# untitled.net
KiCad netlist of a schematic drawn in EAGLE
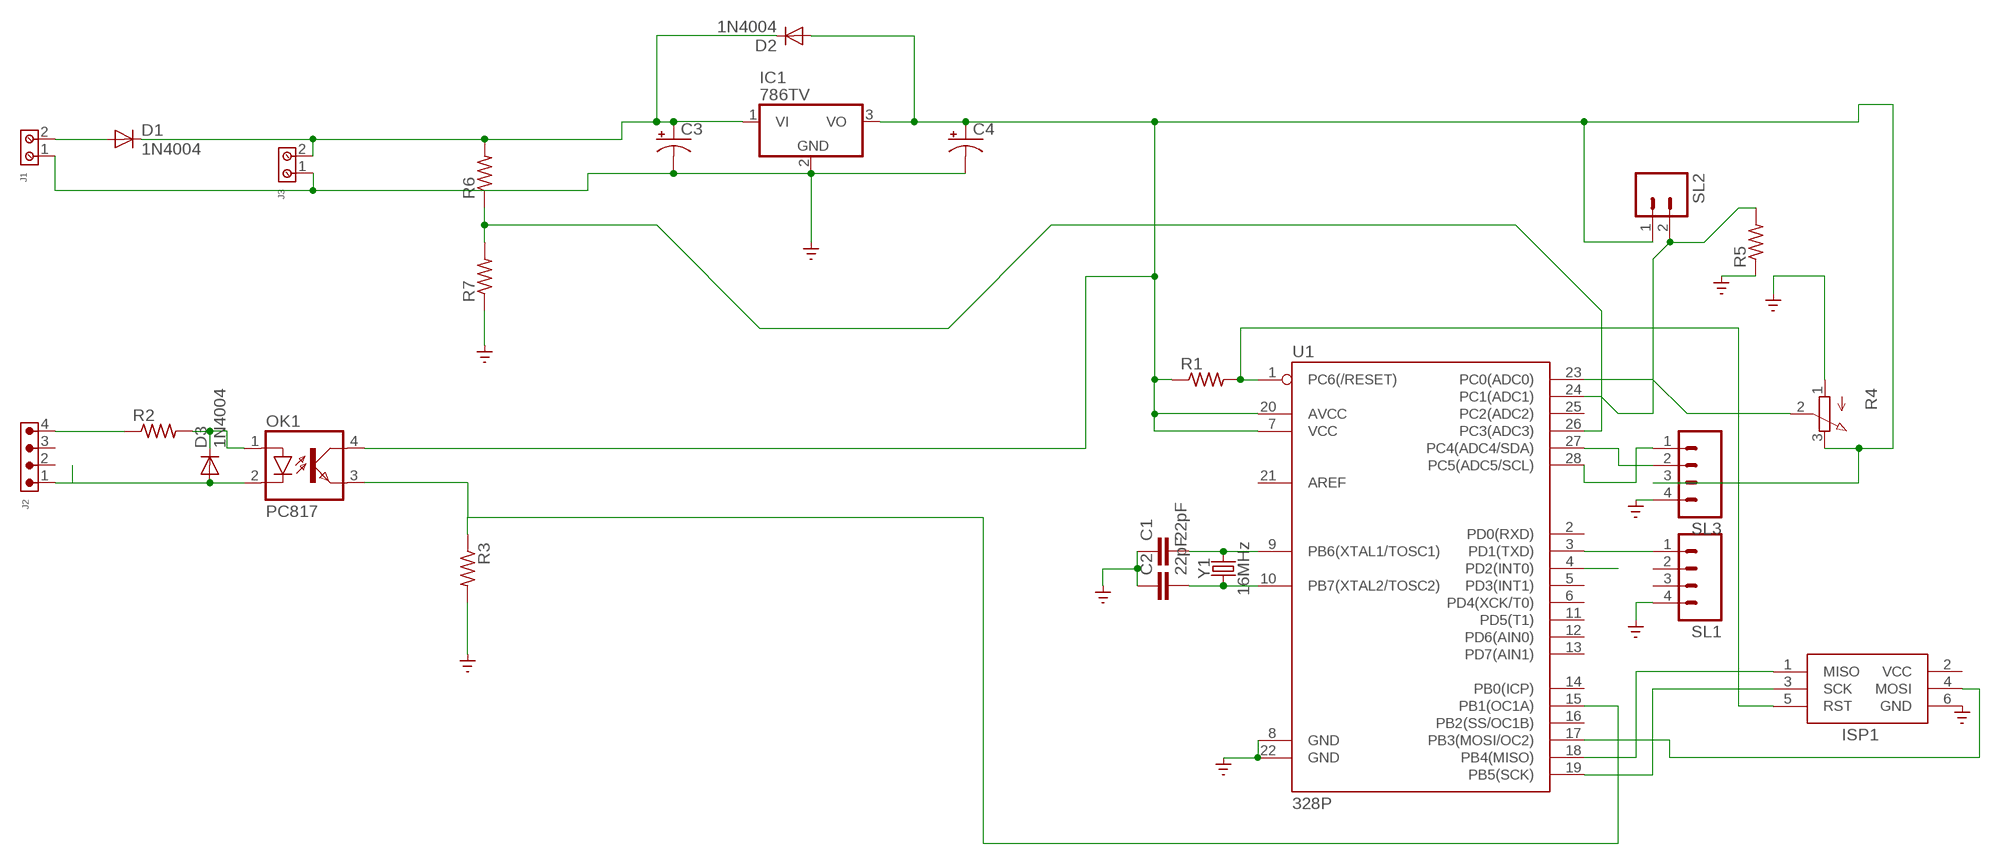
[diagram p0: schematic, sheet 1]

(export (version "E")
  (design (tool "Eeschema 10.0.6"))
  (components
    (comp (ref "C1")
      (value "22pF")
      (footprint "eagle-import:CAP-PTH-2.54")
      (libsource (lib "eagle-import") (part "22PF-PTH-2.54MM-200V-5%"))
    )
    (comp (ref "C2")
      (value "22pF")
      (footprint "eagle-import:CAP-PTH-2.54")
      (libsource (lib "eagle-import") (part "22PF-PTH-2.54MM-200V-5%"))
    )
    (comp (ref "C3")
      (value "CAPACITOR-PE5-10.5")
      (footprint "eagle-import:E5-10,5")
      (libsource (lib "eagle-import") (part "CAPACITOR-PE5-10.5"))
    )
    (comp (ref "C4")
      (value "CAPACITOR-PE5-6")
      (footprint "eagle-import:E5-6")
      (libsource (lib "eagle-import") (part "CAPACITOR-PE5-6"))
    )
    (comp (ref "D1")
      (value "1N4004")
      (footprint "eagle-import:DO41-10")
      (libsource (lib "eagle-import") (part "1N4004"))
    )
    (comp (ref "D2")
      (value "1N4004")
      (footprint "eagle-import:DO41-10")
      (libsource (lib "eagle-import") (part "1N4004"))
    )
    (comp (ref "D3")
      (value "1N4004")
      (footprint "eagle-import:DO41-10")
      (libsource (lib "eagle-import") (part "1N4004"))
    )
    (comp (ref "IC1")
      (value "786TV")
      (footprint "eagle-import:TO220V")
      (libsource (lib "eagle-import") (part "78TV6"))
    )
    (comp (ref "ISP1")
      (value "AVRISP-6")
      (footprint "eagle-import:AVRISP")
      (libsource (lib "eagle-import") (part "AVRISP-6"))
    )
    (comp (ref "J1")
      (value "691213710002")
      (footprint "eagle-import:691213710002")
      (libsource (lib "eagle-import") (part "691213710002"))
    )
    (comp (ref "J2")
      (value "691305530004")
      (footprint "eagle-import:691305530004")
      (libsource (lib "eagle-import") (part "691305530004"))
    )
    (comp (ref "J3")
      (value "691213710002")
      (footprint "eagle-import:691213710002")
      (libsource (lib "eagle-import") (part "691213710002"))
    )
    (comp (ref "OK1")
      (value "PC817")
      (footprint "eagle-import:DIL04")
      (fields (field (name "MPN") "PC817X4J000F"))
      (libsource (lib "eagle-import") (part "PC817"))
    )
    (comp (ref "R1")
      (value "R-US_0207/9")
      (footprint "eagle-import:0207_9")
      (libsource (lib "eagle-import") (part "R-US_0207/9"))
    )
    (comp (ref "R2")
      (value "R-US_0207/9")
      (footprint "eagle-import:0207_9")
      (libsource (lib "eagle-import") (part "R-US_0207/9"))
    )
    (comp (ref "R3")
      (value "R-US_0207/9")
      (footprint "eagle-import:0207_9")
      (libsource (lib "eagle-import") (part "R-US_0207/9"))
    )
    (comp (ref "R4")
      (value "3RP/1610N")
      (footprint "eagle-import:3RP_1610N")
      (libsource (lib "eagle-import") (part "3RP/1610N"))
    )
    (comp (ref "R5")
      (value "R-US_0207/9")
      (footprint "eagle-import:0207_9")
      (libsource (lib "eagle-import") (part "R-US_0207/9"))
    )
    (comp (ref "R6")
      (value "R-US_0207/9")
      (footprint "eagle-import:0207_9")
      (libsource (lib "eagle-import") (part "R-US_0207/9"))
    )
    (comp (ref "R7")
      (value "R-US_0207/9")
      (footprint "eagle-import:0207_9")
      (libsource (lib "eagle-import") (part "R-US_0207/9"))
    )
    (comp (ref "SL1")
      (value "M04")
      (footprint "eagle-import:04P")
      (libsource (lib "eagle-import") (part "M04"))
    )
    (comp (ref "SL2")
      (value "M02")
      (footprint "eagle-import:02P")
      (libsource (lib "eagle-import") (part "M02"))
    )
    (comp (ref "SL3")
      (value "M04")
      (footprint "eagle-import:04P")
      (libsource (lib "eagle-import") (part "M04"))
    )
    (comp (ref "U1")
      (value "328P")
      (footprint "eagle-import:DIP28")
      (libsource (lib "eagle-import") (part "ATMEGA328P_PDIP"))
    )
    (comp (ref "Y1")
      (value "16MHz")
      (footprint "eagle-import:HC49US")
      (libsource (lib "eagle-import") (part "CRYSTAL-16MHZPTH-HC49US"))
    )
  )
  (nets
    (net (code "1") (name "/VCC") (class "Default")
      (node (ref "ISP1") (pin "2") (pinfunction "VCC_2") (pintype "power_in"))
    )
    (net (code "2") (name "Net-(D1-PadA)") (class "Default")
      (node (ref "D1") (pin "A") (pinfunction "A_A") (pintype "passive"))
      (node (ref "J1") (pin "2") (pinfunction "2_2") (pintype "passive"))
    )
    (net (code "3") (name "Net-(IC1-VI)") (class "Default")
      (node (ref "C3") (pin "+") (pinfunction "+_+") (pintype "passive"))
      (node (ref "D1") (pin "C") (pinfunction "C_C") (pintype "passive"))
      (node (ref "D2") (pin "C") (pinfunction "C_C") (pintype "passive"))
      (node (ref "IC1") (pin "1") (pinfunction "VI_1") (pintype "input"))
      (node (ref "J3") (pin "2") (pinfunction "2_2") (pintype "passive"))
      (node (ref "R6") (pin "2") (pinfunction "2_2") (pintype "passive"))
    )
    (net (code "4") (name "Net-(IC1-VO)") (class "Default")
      (node (ref "C4") (pin "+") (pinfunction "+_+") (pintype "passive"))
      (node (ref "D2") (pin "A") (pinfunction "A_A") (pintype "passive"))
      (node (ref "IC1") (pin "3") (pinfunction "VO_3") (pintype "passive"))
      (node (ref "OK1") (pin "4") (pinfunction "COL_4") (pintype "passive"))
      (node (ref "R1") (pin "1") (pinfunction "1_1") (pintype "passive"))
      (node (ref "R4") (pin "3") (pinfunction "E_3") (pintype "passive"))
      (node (ref "SL2") (pin "1") (pinfunction "1_1") (pintype "passive"))
      (node (ref "SL3") (pin "3") (pinfunction "3_3") (pintype "passive"))
      (node (ref "U1") (pin "20") (pinfunction "AVCC_20") (pintype "bidirectional"))
      (node (ref "U1") (pin "7") (pinfunction "VCC_7") (pintype "bidirectional"))
    )
    (net (code "5") (name "Net-(ISP1-MISO)") (class "Default")
      (node (ref "ISP1") (pin "1") (pinfunction "MISO_1") (pintype "input"))
      (node (ref "U1") (pin "18") (pinfunction "PB4(MISO)_18") (pintype "bidirectional"))
    )
    (net (code "6") (name "Net-(ISP1-MOSI)") (class "Default")
      (node (ref "ISP1") (pin "4") (pinfunction "MOSI_4") (pintype "output"))
      (node (ref "U1") (pin "17") (pinfunction "PB3(MOSI/OC2)_17") (pintype "bidirectional"))
    )
    (net (code "7") (name "Net-(ISP1-RST)") (class "Default")
      (node (ref "ISP1") (pin "5") (pinfunction "RST_5") (pintype "output"))
      (node (ref "R1") (pin "2") (pinfunction "2_2") (pintype "passive"))
      (node (ref "U1") (pin "1") (pinfunction "PC6(/RESET)_1") (pintype "bidirectional"))
    )
    (net (code "8") (name "Net-(ISP1-SCK)") (class "Default")
      (node (ref "ISP1") (pin "3") (pinfunction "SCK_3") (pintype "output"))
      (node (ref "U1") (pin "19") (pinfunction "PB5(SCK)_19") (pintype "bidirectional"))
    )
    (net (code "9") (name "Net-(J2-Pad4)") (class "Default")
      (node (ref "J2") (pin "4") (pinfunction "4_4") (pintype "passive"))
      (node (ref "R2") (pin "1") (pinfunction "1_1") (pintype "passive"))
    )
    (net (code "10") (name "Net-(OK1-A)") (class "Default")
      (node (ref "D3") (pin "C") (pinfunction "C_C") (pintype "passive"))
      (node (ref "OK1") (pin "1") (pinfunction "A_1") (pintype "passive"))
      (node (ref "R2") (pin "2") (pinfunction "2_2") (pintype "passive"))
    )
    (net (code "11") (name "Net-(OK1-C)") (class "Default")
      (node (ref "D3") (pin "A") (pinfunction "A_A") (pintype "passive"))
      (node (ref "J2") (pin "1") (pinfunction "1_1") (pintype "passive"))
      (node (ref "OK1") (pin "2") (pinfunction "C_2") (pintype "passive"))
    )
    (net (code "12") (name "Net-(OK1-EMIT)") (class "Default")
      (node (ref "OK1") (pin "3") (pinfunction "EMIT_3") (pintype "passive"))
      (node (ref "R3") (pin "1") (pinfunction "1_1") (pintype "passive"))
      (node (ref "U1") (pin "15") (pinfunction "PB1(OC1A)_15") (pintype "bidirectional"))
    )
    (net (code "13") (name "Net-(R4-S)") (class "Default")
      (node (ref "R4") (pin "2") (pinfunction "S_2") (pintype "passive"))
      (node (ref "U1") (pin "23") (pinfunction "PC0(ADC0)_23") (pintype "bidirectional"))
    )
    (net (code "14") (name "Net-(U1-PB6(XTAL1{slash}TOSC1))") (class "Default")
      (node (ref "C1") (pin "2") (pinfunction "2_2") (pintype "passive"))
      (node (ref "U1") (pin "9") (pinfunction "PB6(XTAL1/TOSC1)_9") (pintype "bidirectional"))
      (node (ref "Y1") (pin "2") (pinfunction "2_2") (pintype "passive"))
    )
    (net (code "15") (name "Net-(U1-PB7(XTAL2{slash}TOSC2))") (class "Default")
      (node (ref "C2") (pin "2") (pinfunction "2_2") (pintype "passive"))
      (node (ref "U1") (pin "10") (pinfunction "PB7(XTAL2/TOSC2)_10") (pintype "bidirectional"))
      (node (ref "Y1") (pin "1") (pinfunction "1_1") (pintype "passive"))
    )
    (net (code "16") (name "Net-(U1-PC1(ADC1))") (class "Default")
      (node (ref "R5") (pin "2") (pinfunction "2_2") (pintype "passive"))
      (node (ref "SL2") (pin "2") (pinfunction "2_2") (pintype "passive"))
      (node (ref "U1") (pin "24") (pinfunction "PC1(ADC1)_24") (pintype "bidirectional"))
    )
    (net (code "17") (name "Net-(U1-PC3(ADC3))") (class "Default")
      (node (ref "R6") (pin "1") (pinfunction "1_1") (pintype "passive"))
      (node (ref "R7") (pin "2") (pinfunction "2_2") (pintype "passive"))
      (node (ref "U1") (pin "26") (pinfunction "PC3(ADC3)_26") (pintype "bidirectional"))
    )
    (net (code "18") (name "Net-(U1-PC4(ADC4{slash}SDA))") (class "Default")
      (node (ref "SL3") (pin "2") (pinfunction "2_2") (pintype "passive"))
      (node (ref "U1") (pin "27") (pinfunction "PC4(ADC4/SDA)_27") (pintype "bidirectional"))
    )
    (net (code "19") (name "Net-(U1-PC5(ADC5{slash}SCL))") (class "Default")
      (node (ref "SL3") (pin "1") (pinfunction "1_1") (pintype "passive"))
      (node (ref "U1") (pin "28") (pinfunction "PC5(ADC5/SCL)_28") (pintype "bidirectional"))
    )
    (net (code "20") (name "Net-(U1-PD1(TXD))") (class "Default")
      (node (ref "SL1") (pin "1") (pinfunction "1_1") (pintype "passive"))
      (node (ref "U1") (pin "3") (pinfunction "PD1(TXD)_3") (pintype "bidirectional"))
    )
    (net (code "21") (name "SUPPLY_BRASTAN_GND_") (class "Default")
      (node (ref "C1") (pin "1") (pinfunction "1_1") (pintype "passive"))
      (node (ref "C2") (pin "1") (pinfunction "1_1") (pintype "passive"))
      (node (ref "C3") (pin "-") (pinfunction "-_-") (pintype "passive"))
      (node (ref "C4") (pin "-") (pinfunction "-_-") (pintype "passive"))
      (node (ref "IC1") (pin "2") (pinfunction "GND_2") (pintype "passive"))
      (node (ref "ISP1") (pin "6") (pinfunction "GND_6") (pintype "power_in"))
      (node (ref "J1") (pin "1") (pinfunction "1_1") (pintype "passive"))
      (node (ref "J3") (pin "1") (pinfunction "1_1") (pintype "passive"))
      (node (ref "R3") (pin "2") (pinfunction "2_2") (pintype "passive"))
      (node (ref "R4") (pin "1") (pinfunction "A_1") (pintype "passive"))
      (node (ref "R5") (pin "1") (pinfunction "1_1") (pintype "passive"))
      (node (ref "R7") (pin "1") (pinfunction "1_1") (pintype "passive"))
      (node (ref "SL1") (pin "4") (pinfunction "4_4") (pintype "passive"))
      (node (ref "SL3") (pin "4") (pinfunction "4_4") (pintype "passive"))
      (node (ref "U1") (pin "22") (pinfunction "GND_22") (pintype "bidirectional"))
      (node (ref "U1") (pin "8") (pinfunction "GND_8") (pintype "bidirectional"))
    )
    (net (code "22") (name "unconnected-(J2-Pad2)") (class "Default")
      (node (ref "J2") (pin "2") (pinfunction "2_2") (pintype "passive"))
    )
    (net (code "23") (name "unconnected-(J2-Pad3)") (class "Default")
      (node (ref "J2") (pin "3") (pinfunction "3_3") (pintype "passive"))
    )
    (net (code "24") (name "unconnected-(SL1-Pad2)") (class "Default")
      (node (ref "SL1") (pin "2") (pinfunction "2_2") (pintype "passive"))
    )
    (net (code "25") (name "unconnected-(SL1-Pad3)") (class "Default")
      (node (ref "SL1") (pin "3") (pinfunction "3_3") (pintype "passive"))
    )
    (net (code "26") (name "unconnected-(U1-AREF-Pad21)") (class "Default")
      (node (ref "U1") (pin "21") (pinfunction "AREF_21") (pintype "bidirectional"))
    )
    (net (code "27") (name "unconnected-(U1-PB0(ICP)-Pad14)") (class "Default")
      (node (ref "U1") (pin "14") (pinfunction "PB0(ICP)_14") (pintype "bidirectional"))
    )
    (net (code "28") (name "unconnected-(U1-PB2(SS{slash}OC1B)-Pad16)") (class "Default")
      (node (ref "U1") (pin "16") (pinfunction "PB2(SS/OC1B)_16") (pintype "bidirectional"))
    )
    (net (code "29") (name "unconnected-(U1-PC2(ADC2)-Pad25)") (class "Default")
      (node (ref "U1") (pin "25") (pinfunction "PC2(ADC2)_25") (pintype "bidirectional"))
    )
    (net (code "30") (name "unconnected-(U1-PD0(RXD)-Pad2)") (class "Default")
      (node (ref "U1") (pin "2") (pinfunction "PD0(RXD)_2") (pintype "bidirectional"))
    )
    (net (code "31") (name "unconnected-(U1-PD2(INT0)-Pad4)") (class "Default")
      (node (ref "U1") (pin "4") (pinfunction "PD2(INT0)_4") (pintype "bidirectional"))
    )
    (net (code "32") (name "unconnected-(U1-PD3(INT1)-Pad5)") (class "Default")
      (node (ref "U1") (pin "5") (pinfunction "PD3(INT1)_5") (pintype "bidirectional"))
    )
    (net (code "33") (name "unconnected-(U1-PD4(XCK{slash}T0)-Pad6)") (class "Default")
      (node (ref "U1") (pin "6") (pinfunction "PD4(XCK/T0)_6") (pintype "bidirectional"))
    )
    (net (code "34") (name "unconnected-(U1-PD5(T1)-Pad11)") (class "Default")
      (node (ref "U1") (pin "11") (pinfunction "PD5(T1)_11") (pintype "bidirectional"))
    )
    (net (code "35") (name "unconnected-(U1-PD6(AIN0)-Pad12)") (class "Default")
      (node (ref "U1") (pin "12") (pinfunction "PD6(AIN0)_12") (pintype "bidirectional"))
    )
    (net (code "36") (name "unconnected-(U1-PD7(AIN1)-Pad13)") (class "Default")
      (node (ref "U1") (pin "13") (pinfunction "PD7(AIN1)_13") (pintype "bidirectional"))
    )
  )
)
